# TommyPROM-uno.net
KiCad netlist of a schematic drawn in EAGLE
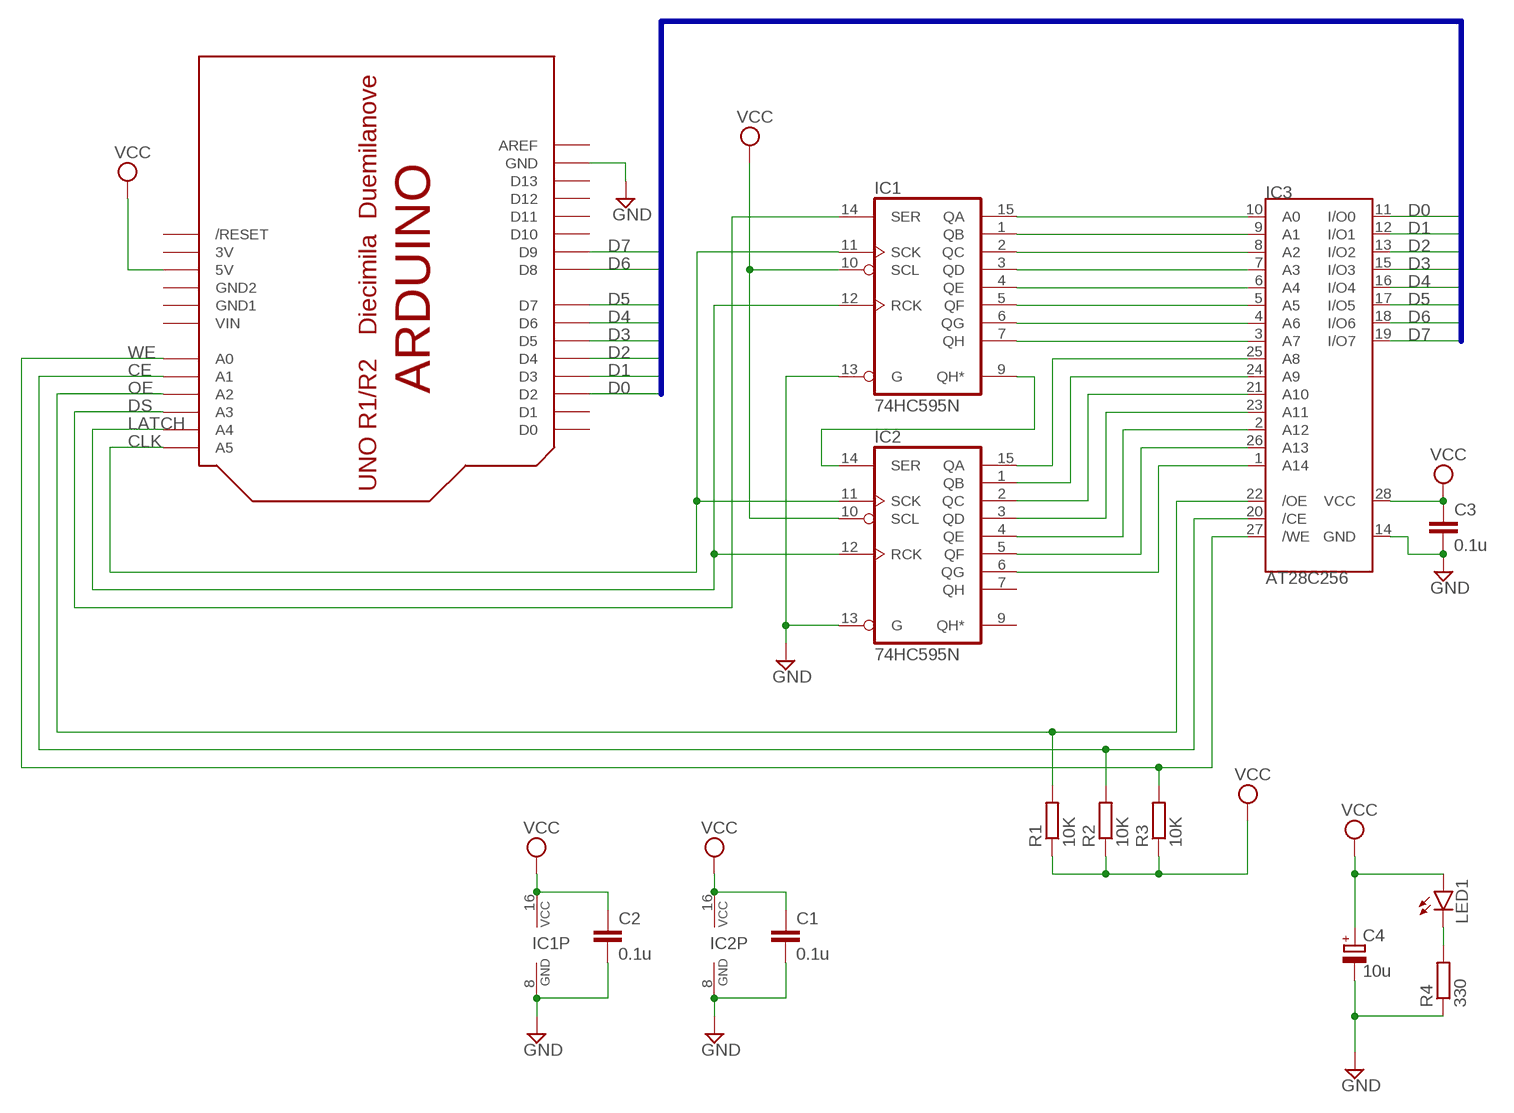
[diagram p0: schematic, sheet 1]

(export (version "E")
  (design (tool "Eeschema 10.0.6"))
  (components
    (comp (ref "C1")
      (value "0.1u")
      (footprint "eagle-import:C025-025X050")
      (libsource (lib "eagle-import") (part "C-EU025-025X050"))
    )
    (comp (ref "C2")
      (value "0.1u")
      (footprint "eagle-import:C025-025X050")
      (libsource (lib "eagle-import") (part "C-EU025-025X050"))
    )
    (comp (ref "C3")
      (value "0.1u")
      (footprint "eagle-import:C025-025X050")
      (libsource (lib "eagle-import") (part "C-EU025-025X050"))
    )
    (comp (ref "C4")
      (value "10u")
      (footprint "eagle-import:E2-5")
      (libsource (lib "eagle-import") (part "CPOL-EUE2-5"))
    )
    (comp (ref "IC1")
      (value "74HC595N")
      (footprint "eagle-import:DIL16")
      (libsource (lib "eagle-import") (part "74595NHC"))
    )
    (comp (ref "IC2")
      (value "74HC595N")
      (footprint "eagle-import:DIL16")
      (libsource (lib "eagle-import") (part "74595NHC"))
    )
    (comp (ref "IC3")
      (value "AT28C256")
      (footprint "eagle-import:DIL28-6")
      (libsource (lib "eagle-import") (part "AT28C256-28DIP"))
    )
    (comp (ref "LED1")
      (value "LED5MM")
      (footprint "eagle-import:LED5MM")
      (libsource (lib "eagle-import") (part "LED5MM"))
    )
    (comp (ref "R1")
      (value "10K")
      (footprint "eagle-import:0204_7")
      (libsource (lib "eagle-import") (part "R-EU_0204/7"))
    )
    (comp (ref "R2")
      (value "10K")
      (footprint "eagle-import:0204_7")
      (libsource (lib "eagle-import") (part "R-EU_0204/7"))
    )
    (comp (ref "R3")
      (value "10K")
      (footprint "eagle-import:0204_7")
      (libsource (lib "eagle-import") (part "R-EU_0204/7"))
    )
    (comp (ref "R4")
      (value "330")
      (footprint "eagle-import:0204_7")
      (libsource (lib "eagle-import") (part "R-EU_0204/7"))
    )
    (comp (ref "U$1")
      (value "ARDUINO-BPLACE")
      (footprint "eagle-import:ARDUINO-BPLACE")
      (libsource (lib "eagle-import") (part "ARDUINO-BPLACE"))
    )
  )
  (nets
    (net (code "1") (name "/3V") (class "Default")
      (node (ref "U$1") (pin "3V") (pinfunction "3V_3V") (pintype "power_in"))
    )
    (net (code "2") (name "/CE") (class "Default")
      (node (ref "IC3") (pin "20") (pinfunction "/CE_20") (pintype "input"))
      (node (ref "R2") (pin "2") (pinfunction "2_2") (pintype "passive"))
      (node (ref "U$1") (pin "A1") (pinfunction "A1_A1") (pintype "bidirectional"))
    )
    (net (code "3") (name "/CLK") (class "Default")
      (node (ref "IC1") (pin "11") (pinfunction "SCK_11") (pintype "input"))
      (node (ref "IC2") (pin "11") (pinfunction "SCK_11") (pintype "input"))
      (node (ref "U$1") (pin "A5") (pinfunction "A5_A5") (pintype "bidirectional"))
    )
    (net (code "4") (name "/D0") (class "Default")
      (node (ref "IC3") (pin "11") (pinfunction "I/O0_11") (pintype "bidirectional"))
      (node (ref "U$1") (pin "D2") (pinfunction "D2_D2") (pintype "bidirectional"))
    )
    (net (code "5") (name "/D1") (class "Default")
      (node (ref "IC3") (pin "12") (pinfunction "I/O1_12") (pintype "bidirectional"))
      (node (ref "U$1") (pin "D3") (pinfunction "D3_D3") (pintype "bidirectional"))
    )
    (net (code "6") (name "/D2") (class "Default")
      (node (ref "IC3") (pin "13") (pinfunction "I/O2_13") (pintype "bidirectional"))
      (node (ref "U$1") (pin "D4") (pinfunction "D4_D4") (pintype "bidirectional"))
    )
    (net (code "7") (name "/D3") (class "Default")
      (node (ref "IC3") (pin "15") (pinfunction "I/O3_15") (pintype "bidirectional"))
      (node (ref "U$1") (pin "D5") (pinfunction "D5_D5") (pintype "bidirectional"))
    )
    (net (code "8") (name "/D4") (class "Default")
      (node (ref "IC3") (pin "16") (pinfunction "I/O4_16") (pintype "bidirectional"))
      (node (ref "U$1") (pin "D6") (pinfunction "D6_D6") (pintype "bidirectional"))
    )
    (net (code "9") (name "/D5") (class "Default")
      (node (ref "IC3") (pin "17") (pinfunction "I/O5_17") (pintype "bidirectional"))
      (node (ref "U$1") (pin "D7") (pinfunction "D7_D7") (pintype "bidirectional"))
    )
    (net (code "10") (name "/D6") (class "Default")
      (node (ref "IC3") (pin "18") (pinfunction "I/O6_18") (pintype "bidirectional"))
      (node (ref "U$1") (pin "D8") (pinfunction "D8_D8") (pintype "bidirectional"))
    )
    (net (code "11") (name "/D7") (class "Default")
      (node (ref "IC3") (pin "19") (pinfunction "I/O7_19") (pintype "bidirectional"))
      (node (ref "U$1") (pin "D9") (pinfunction "D9_D9") (pintype "bidirectional"))
    )
    (net (code "12") (name "/DS") (class "Default")
      (node (ref "IC1") (pin "14") (pinfunction "SER_14") (pintype "input"))
      (node (ref "U$1") (pin "A3") (pinfunction "A3_A3") (pintype "bidirectional"))
    )
    (net (code "14") (name "/GND1") (class "Default")
      (node (ref "U$1") (pin "GND1") (pinfunction "GND1_GND1") (pintype "power_in"))
    )
    (net (code "15") (name "/GND2") (class "Default")
      (node (ref "U$1") (pin "GND2") (pinfunction "GND2_GND2") (pintype "power_in"))
    )
    (net (code "16") (name "/LATCH") (class "Default")
      (node (ref "IC1") (pin "12") (pinfunction "RCK_12") (pintype "input"))
      (node (ref "IC2") (pin "12") (pinfunction "RCK_12") (pintype "input"))
      (node (ref "U$1") (pin "A4") (pinfunction "A4_A4") (pintype "bidirectional"))
    )
    (net (code "17") (name "/OE") (class "Default")
      (node (ref "IC3") (pin "22") (pinfunction "/OE_22") (pintype "input"))
      (node (ref "R1") (pin "2") (pinfunction "2_2") (pintype "passive"))
      (node (ref "U$1") (pin "A2") (pinfunction "A2_A2") (pintype "bidirectional"))
    )
    (net (code "18") (name "/VIN") (class "Default")
      (node (ref "U$1") (pin "VIN") (pinfunction "VIN_VIN") (pintype "power_in"))
    )
    (net (code "19") (name "/WE") (class "Default")
      (node (ref "IC3") (pin "27") (pinfunction "/WE_27") (pintype "input"))
      (node (ref "R3") (pin "2") (pinfunction "2_2") (pintype "passive"))
      (node (ref "U$1") (pin "A0") (pinfunction "A0_A0") (pintype "bidirectional"))
    )
    (net (code "20") (name "GND") (class "Default")
      (node (ref "C1") (pin "2") (pinfunction "2_2") (pintype "passive"))
      (node (ref "C2") (pin "2") (pinfunction "2_2") (pintype "passive"))
      (node (ref "C3") (pin "2") (pinfunction "2_2") (pintype "passive"))
      (node (ref "C4") (pin "-") (pinfunction "-_-") (pintype "passive"))
      (node (ref "IC1") (pin "13") (pinfunction "G_13") (pintype "input"))
      (node (ref "IC1") (pin "8") (pinfunction "GND_8") (pintype "power_in"))
      (node (ref "IC2") (pin "13") (pinfunction "G_13") (pintype "input"))
      (node (ref "IC2") (pin "8") (pinfunction "GND_8") (pintype "power_in"))
      (node (ref "IC3") (pin "14") (pinfunction "GND_14") (pintype "power_in"))
      (node (ref "R4") (pin "1") (pinfunction "1_1") (pintype "passive"))
      (node (ref "U$1") (pin "GND") (pinfunction "GND_GND") (pintype "power_in"))
    )
    (net (code "21") (name "Net-(IC1A-QA)") (class "Default")
      (node (ref "IC1") (pin "15") (pinfunction "QA_15") (pintype "tri_state"))
      (node (ref "IC3") (pin "10") (pinfunction "A0_10") (pintype "input"))
    )
    (net (code "22") (name "Net-(IC1A-QB)") (class "Default")
      (node (ref "IC1") (pin "1") (pinfunction "QB_1") (pintype "tri_state"))
      (node (ref "IC3") (pin "9") (pinfunction "A1_9") (pintype "input"))
    )
    (net (code "23") (name "Net-(IC1A-QC)") (class "Default")
      (node (ref "IC1") (pin "2") (pinfunction "QC_2") (pintype "tri_state"))
      (node (ref "IC3") (pin "8") (pinfunction "A2_8") (pintype "input"))
    )
    (net (code "24") (name "Net-(IC1A-QD)") (class "Default")
      (node (ref "IC1") (pin "3") (pinfunction "QD_3") (pintype "tri_state"))
      (node (ref "IC3") (pin "7") (pinfunction "A3_7") (pintype "input"))
    )
    (net (code "25") (name "Net-(IC1A-QE)") (class "Default")
      (node (ref "IC1") (pin "4") (pinfunction "QE_4") (pintype "tri_state"))
      (node (ref "IC3") (pin "6") (pinfunction "A4_6") (pintype "input"))
    )
    (net (code "26") (name "Net-(IC1A-QF)") (class "Default")
      (node (ref "IC1") (pin "5") (pinfunction "QF_5") (pintype "tri_state"))
      (node (ref "IC3") (pin "5") (pinfunction "A5_5") (pintype "input"))
    )
    (net (code "27") (name "Net-(IC1A-QG)") (class "Default")
      (node (ref "IC1") (pin "6") (pinfunction "QG_6") (pintype "tri_state"))
      (node (ref "IC3") (pin "4") (pinfunction "A6_4") (pintype "input"))
    )
    (net (code "28") (name "Net-(IC1A-QH)") (class "Default")
      (node (ref "IC1") (pin "7") (pinfunction "QH_7") (pintype "tri_state"))
      (node (ref "IC3") (pin "3") (pinfunction "A7_3") (pintype "input"))
    )
    (net (code "29") (name "Net-(IC1A-QH*)") (class "Default")
      (node (ref "IC1") (pin "9") (pinfunction "QH*_9") (pintype "tri_state"))
      (node (ref "IC2") (pin "14") (pinfunction "SER_14") (pintype "input"))
    )
    (net (code "30") (name "Net-(IC2A-QA)") (class "Default")
      (node (ref "IC2") (pin "15") (pinfunction "QA_15") (pintype "tri_state"))
      (node (ref "IC3") (pin "25") (pinfunction "A8_25") (pintype "input"))
    )
    (net (code "31") (name "Net-(IC2A-QB)") (class "Default")
      (node (ref "IC2") (pin "1") (pinfunction "QB_1") (pintype "tri_state"))
      (node (ref "IC3") (pin "24") (pinfunction "A9_24") (pintype "input"))
    )
    (net (code "32") (name "Net-(IC2A-QC)") (class "Default")
      (node (ref "IC2") (pin "2") (pinfunction "QC_2") (pintype "tri_state"))
      (node (ref "IC3") (pin "21") (pinfunction "A10_21") (pintype "input"))
    )
    (net (code "33") (name "Net-(IC2A-QD)") (class "Default")
      (node (ref "IC2") (pin "3") (pinfunction "QD_3") (pintype "tri_state"))
      (node (ref "IC3") (pin "23") (pinfunction "A11_23") (pintype "input"))
    )
    (net (code "34") (name "Net-(IC2A-QE)") (class "Default")
      (node (ref "IC2") (pin "4") (pinfunction "QE_4") (pintype "tri_state"))
      (node (ref "IC3") (pin "2") (pinfunction "A12_2") (pintype "input"))
    )
    (net (code "35") (name "Net-(IC2A-QF)") (class "Default")
      (node (ref "IC2") (pin "5") (pinfunction "QF_5") (pintype "tri_state"))
      (node (ref "IC3") (pin "26") (pinfunction "A13_26") (pintype "input"))
    )
    (net (code "36") (name "Net-(IC2A-QG)") (class "Default")
      (node (ref "IC2") (pin "6") (pinfunction "QG_6") (pintype "tri_state"))
      (node (ref "IC3") (pin "1") (pinfunction "A14_1") (pintype "input"))
    )
    (net (code "37") (name "Net-(LED1-C)") (class "Default")
      (node (ref "LED1") (pin "K") (pinfunction "C_K") (pintype "passive"))
      (node (ref "R4") (pin "2") (pinfunction "2_2") (pintype "passive"))
    )
    (net (code "38") (name "VCC") (class "Default")
      (node (ref "C1") (pin "1") (pinfunction "1_1") (pintype "passive"))
      (node (ref "C2") (pin "1") (pinfunction "1_1") (pintype "passive"))
      (node (ref "C3") (pin "1") (pinfunction "1_1") (pintype "passive"))
      (node (ref "C4") (pin "+") (pinfunction "+_+") (pintype "passive"))
      (node (ref "IC1") (pin "10") (pinfunction "SCL_10") (pintype "input"))
      (node (ref "IC1") (pin "16") (pinfunction "VCC_16") (pintype "power_in"))
      (node (ref "IC2") (pin "10") (pinfunction "SCL_10") (pintype "input"))
      (node (ref "IC2") (pin "16") (pinfunction "VCC_16") (pintype "power_in"))
      (node (ref "IC3") (pin "28") (pinfunction "VCC_28") (pintype "power_in"))
      (node (ref "LED1") (pin "A") (pinfunction "A_A") (pintype "passive"))
      (node (ref "R1") (pin "1") (pinfunction "1_1") (pintype "passive"))
      (node (ref "R2") (pin "1") (pinfunction "1_1") (pintype "passive"))
      (node (ref "R3") (pin "1") (pinfunction "1_1") (pintype "passive"))
      (node (ref "U$1") (pin "5V") (pinfunction "5V_5V") (pintype "power_in"))
    )
    (net (code "39") (name "unconnected-(IC2A-QH*-Pad9)") (class "Default")
      (node (ref "IC2") (pin "9") (pinfunction "QH*_9") (pintype "tri_state"))
    )
    (net (code "40") (name "unconnected-(IC2A-QH-Pad7)") (class "Default")
      (node (ref "IC2") (pin "7") (pinfunction "QH_7") (pintype "tri_state"))
    )
    (net (code "41") (name "unconnected-(U$1-PadAREF)") (class "Default")
      (node (ref "U$1") (pin "AREF") (pinfunction "AREF_AREF") (pintype "bidirectional"))
    )
    (net (code "42") (name "unconnected-(U$1-PadD0)") (class "Default")
      (node (ref "U$1") (pin "D0") (pinfunction "D0_D0") (pintype "bidirectional"))
    )
    (net (code "43") (name "unconnected-(U$1-PadD1)") (class "Default")
      (node (ref "U$1") (pin "D1") (pinfunction "D1_D1") (pintype "bidirectional"))
    )
    (net (code "44") (name "unconnected-(U$1-PadD10)") (class "Default")
      (node (ref "U$1") (pin "D10") (pinfunction "D10_D10") (pintype "bidirectional"))
    )
    (net (code "45") (name "unconnected-(U$1-PadD11)") (class "Default")
      (node (ref "U$1") (pin "D11") (pinfunction "D11_D11") (pintype "bidirectional"))
    )
    (net (code "46") (name "unconnected-(U$1-PadD12)") (class "Default")
      (node (ref "U$1") (pin "D12") (pinfunction "D12_D12") (pintype "bidirectional"))
    )
    (net (code "47") (name "unconnected-(U$1-PadD13)") (class "Default")
      (node (ref "U$1") (pin "D13") (pinfunction "D13_D13") (pintype "bidirectional"))
    )
    (net (code "48") (name "unconnected-(U$1-{slash}RESET-PadRESET)") (class "Default")
      (node (ref "U$1") (pin "RESET") (pinfunction "/RESET_RESET") (pintype "bidirectional"))
    )
  )
)
